# ESC_connections.net
KiCad netlist of a schematic drawn in Altium Designer
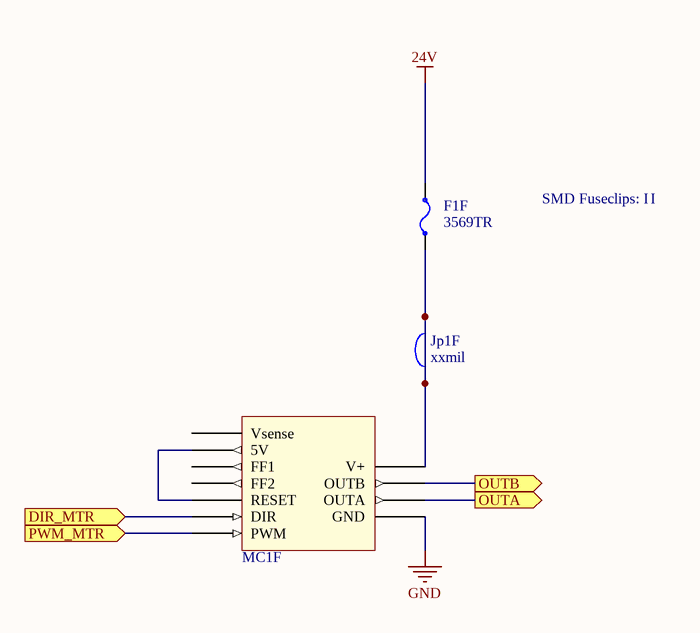
[diagram p0: ESC connections.SchDoc]

(export (version "E")
  (design (tool "Eeschema 10.0.6"))
  (components
    (comp (ref "F1F")
      (value "3569TR")
      (footprint "Horizontal SMD fuse clip")
      (description "Fuse Clip Assembly")
      (fields (field (name "MANUFACTURER PART NUMBER") "3569TR"))
      (libsource (lib "Keystone SchLib") (part "3569TR"))
    )
    (comp (ref "i10F")
      (value "3569TR (Placeholder)")
      (description "Fuse Clip")
      (fields (field (name "MANUFACTURER PART NUMBER") "3569TR"))
      (libsource (lib "") (part "3569TR (Placeholder)_1"))
    )
    (comp (ref "i11F")
      (value "3569TR (Placeholder)")
      (description "Fuse Clip")
      (fields (field (name "MANUFACTURER PART NUMBER") "3569TR"))
      (libsource (lib "Keystone SchLib") (part "3569TR (Placeholder)"))
    )
    (comp (ref "Jp1F")
      (value "xxmil")
      (footprint "Jumper, 12AWG, 0.6\"")
      (description "Resistor")
      (fields (field (name "Comment") "Jumper"))
      (libsource (lib "URC") (part "Jump"))
    )
    (comp (ref "MC1F")
      (value "Motor Controller")
      (footprint "Pololu 24v12")
      (description "Pololu 24v12 Motor Driver")
      (libsource (lib "URC_Lib") (part "Pololu 24v12"))
    )
  )
  (nets
    (net (code "1") (name "/DIR_MTR") (class "Default")
      (node (ref "MC1F") (pin "DIR") (pinfunction "DIR_DIR") (pintype "input"))
    )
    (net (code "2") (name "/OUTA") (class "Default")
      (node (ref "MC1F") (pin "OUTA") (pinfunction "OUTA_OUTA") (pintype "output"))
    )
    (net (code "3") (name "/OUTB") (class "Default")
      (node (ref "MC1F") (pin "OUTB") (pinfunction "OUTB_OUTB") (pintype "output"))
    )
    (net (code "4") (name "/PWM_MTR") (class "Default")
      (node (ref "MC1F") (pin "PWM") (pinfunction "PWM_PWM") (pintype "input"))
    )
    (net (code "5") (name "24V") (class "Default")
      (node (ref "F1F") (pin "1") (pinfunction "1_1") (pintype "passive"))
    )
    (net (code "6") (name "GND") (class "Default")
      (node (ref "MC1F") (pin "GND") (pinfunction "GND_GND") (pintype "power_in"))
    )
    (net (code "7") (name "Net-(F1F-Pad2)") (class "Default")
      (node (ref "F1F") (pin "2") (pinfunction "2_2") (pintype "passive"))
      (node (ref "Jp1F") (pin "1") (pinfunction "1_1") (pintype "passive"))
      (node (ref "Jp1F") (pin "2") (pinfunction "2_2") (pintype "passive"))
      (node (ref "MC1F") (pin "V+") (pinfunction "V+_V+") (pintype "power_in"))
    )
    (net (code "8") (name "Net-(MC1F-Pad5V)") (class "Default")
      (node (ref "MC1F") (pin "5V") (pinfunction "5V_5V") (pintype "output"))
      (node (ref "MC1F") (pin "RESET") (pinfunction "RESET_RESET") (pintype "passive"))
    )
    (net (code "9") (name "unconnected-(MC1F-PadFF1)") (class "Default")
      (node (ref "MC1F") (pin "FF1") (pinfunction "FF1_FF1") (pintype "output"))
    )
    (net (code "10") (name "unconnected-(MC1F-PadFF2)") (class "Default")
      (node (ref "MC1F") (pin "FF2") (pinfunction "FF2_FF2") (pintype "output"))
    )
    (net (code "11") (name "unconnected-(MC1F-Vsense-PadV+_SENSE)") (class "Default")
      (node (ref "MC1F") (pin "V+_SENSE") (pinfunction "Vsense_V+_SENSE") (pintype "passive"))
    )
  )
)
